# untitled.net
KiCad netlist of a schematic drawn in EAGLE
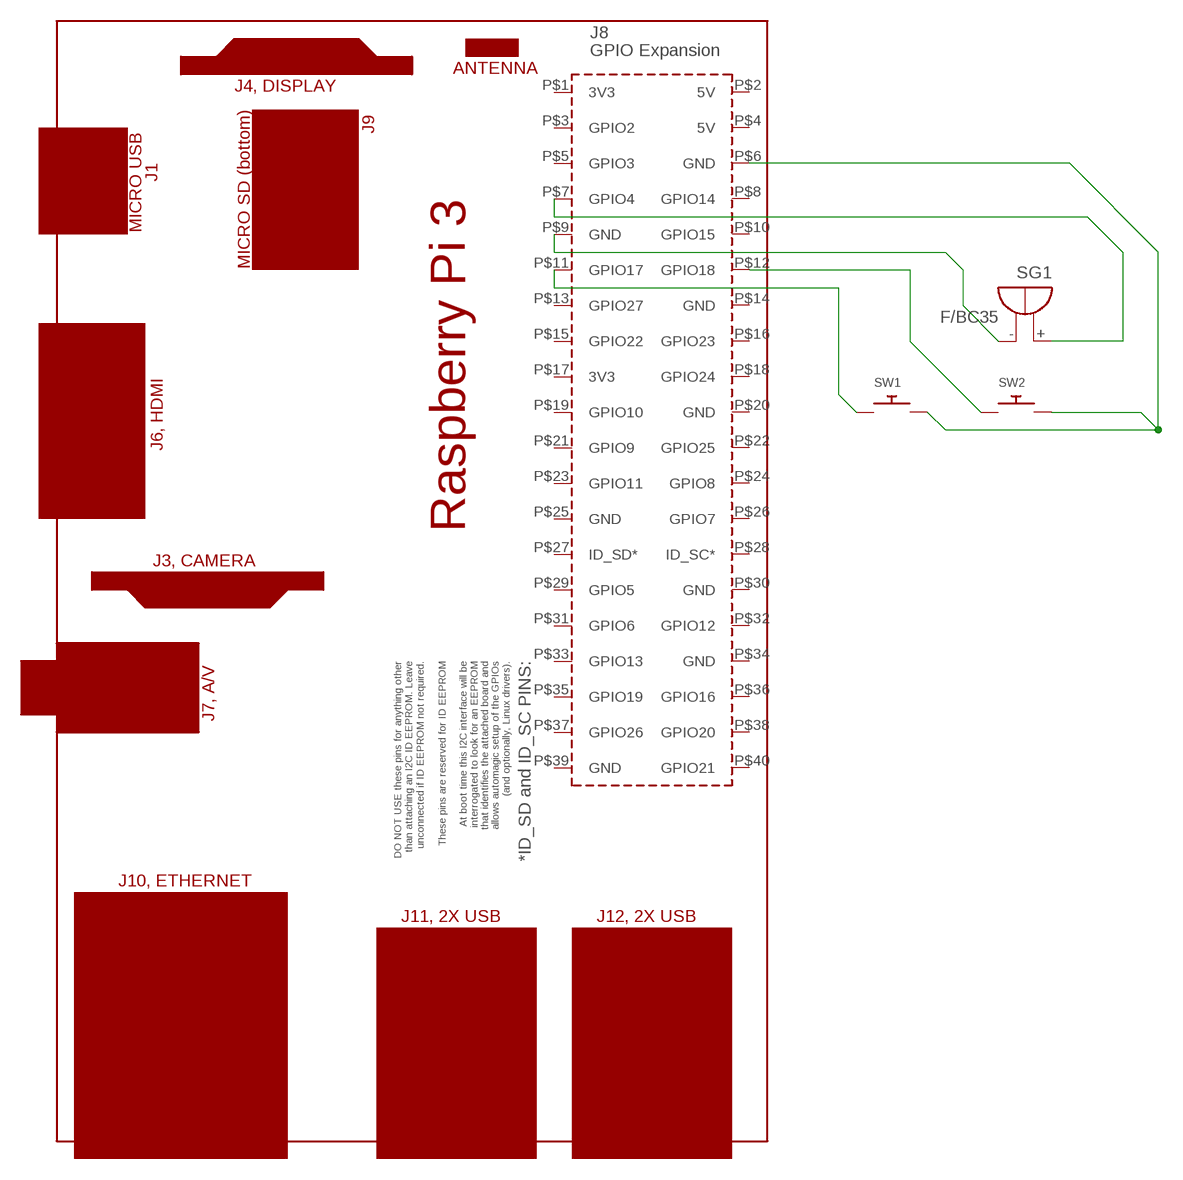
[diagram p0: schematic, sheet 1]

(export (version "E")
  (design (tool "Eeschema 10.0.6"))
  (components
    (comp (ref "PCB1")
      (value "RPI3RPI3")
      (footprint "eagle-import:RPI3")
      (libsource (lib "eagle-import") (part "RPI3RPI3"))
    )
    (comp (ref "SG1")
      (value "F/BC35")
      (footprint "eagle-import:F_BC35")
      (libsource (lib "eagle-import") (part "F/BC35"))
    )
    (comp (ref "SW1")
      (value "SWITCH_PUSHBUTTONSOFTTOUCHSMD_SJ")
      (footprint "eagle-import:PUSHBUTTON_SMD_SJ")
      (libsource (lib "eagle-import") (part "SWITCH_PUSHBUTTONSOFTTOUCHSMD_SJ"))
    )
    (comp (ref "SW2")
      (value "SWITCH_PUSHBUTTONSOFTTOUCHSMD_SJ")
      (footprint "eagle-import:PUSHBUTTON_SMD_SJ")
      (libsource (lib "eagle-import") (part "SWITCH_PUSHBUTTONSOFTTOUCHSMD_SJ"))
    )
  )
  (nets
    (net (code "1") (name "Net-(PCB1-GND-PadP$6)") (class "Default")
      (node (ref "PCB1") (pin "P$6") (pinfunction "GND_P$6") (pintype "bidirectional"))
      (node (ref "SW1") (pin "P$2") (pinfunction "P$2_P$2") (pintype "passive"))
      (node (ref "SW2") (pin "P$2") (pinfunction "P$2_P$2") (pintype "passive"))
    )
    (net (code "2") (name "Net-(PCB1-GND-PadP$9)") (class "Default")
      (node (ref "PCB1") (pin "P$9") (pinfunction "GND_P$9") (pintype "bidirectional"))
      (node (ref "SG1") (pin "-") (pinfunction "-_-") (pintype "passive"))
    )
    (net (code "3") (name "Net-(PCB1-GPIO4)") (class "Default")
      (node (ref "PCB1") (pin "P$7") (pinfunction "GPIO4_P$7") (pintype "bidirectional"))
      (node (ref "SG1") (pin "+") (pinfunction "+_+") (pintype "passive"))
    )
    (net (code "4") (name "Net-(PCB1-GPIO17)") (class "Default")
      (node (ref "PCB1") (pin "P$11") (pinfunction "GPIO17_P$11") (pintype "bidirectional"))
      (node (ref "SW1") (pin "P$1") (pinfunction "P$1_P$1") (pintype "passive"))
    )
    (net (code "5") (name "Net-(PCB1-GPIO18)") (class "Default")
      (node (ref "PCB1") (pin "P$12") (pinfunction "GPIO18_P$12") (pintype "bidirectional"))
      (node (ref "SW2") (pin "P$1") (pinfunction "P$1_P$1") (pintype "passive"))
    )
    (net (code "6") (name "unconnected-(PCB1-3V3-PadP$1)") (class "Default")
      (node (ref "PCB1") (pin "P$1") (pinfunction "3V3_P$1") (pintype "bidirectional"))
    )
    (net (code "7") (name "unconnected-(PCB1-3V3-PadP$17)") (class "Default")
      (node (ref "PCB1") (pin "P$17") (pinfunction "3V3_P$17") (pintype "bidirectional"))
    )
    (net (code "8") (name "unconnected-(PCB1-5V-PadP$2)") (class "Default")
      (node (ref "PCB1") (pin "P$2") (pinfunction "5V_P$2") (pintype "bidirectional"))
    )
    (net (code "9") (name "unconnected-(PCB1-5V-PadP$4)") (class "Default")
      (node (ref "PCB1") (pin "P$4") (pinfunction "5V_P$4") (pintype "bidirectional"))
    )
    (net (code "10") (name "unconnected-(PCB1-GND-PadP$14)") (class "Default")
      (node (ref "PCB1") (pin "P$14") (pinfunction "GND_P$14") (pintype "bidirectional"))
    )
    (net (code "11") (name "unconnected-(PCB1-GND-PadP$20)") (class "Default")
      (node (ref "PCB1") (pin "P$20") (pinfunction "GND_P$20") (pintype "bidirectional"))
    )
    (net (code "12") (name "unconnected-(PCB1-GND-PadP$25)") (class "Default")
      (node (ref "PCB1") (pin "P$25") (pinfunction "GND_P$25") (pintype "bidirectional"))
    )
    (net (code "13") (name "unconnected-(PCB1-GND-PadP$30)") (class "Default")
      (node (ref "PCB1") (pin "P$30") (pinfunction "GND_P$30") (pintype "bidirectional"))
    )
    (net (code "14") (name "unconnected-(PCB1-GND-PadP$34)") (class "Default")
      (node (ref "PCB1") (pin "P$34") (pinfunction "GND_P$34") (pintype "bidirectional"))
    )
    (net (code "15") (name "unconnected-(PCB1-GND-PadP$39)") (class "Default")
      (node (ref "PCB1") (pin "P$39") (pinfunction "GND_P$39") (pintype "bidirectional"))
    )
    (net (code "16") (name "unconnected-(PCB1-GPIO2-PadP$3)") (class "Default")
      (node (ref "PCB1") (pin "P$3") (pinfunction "GPIO2_P$3") (pintype "bidirectional"))
    )
    (net (code "17") (name "unconnected-(PCB1-GPIO3-PadP$5)") (class "Default")
      (node (ref "PCB1") (pin "P$5") (pinfunction "GPIO3_P$5") (pintype "bidirectional"))
    )
    (net (code "18") (name "unconnected-(PCB1-GPIO5-PadP$29)") (class "Default")
      (node (ref "PCB1") (pin "P$29") (pinfunction "GPIO5_P$29") (pintype "bidirectional"))
    )
    (net (code "19") (name "unconnected-(PCB1-GPIO6-PadP$31)") (class "Default")
      (node (ref "PCB1") (pin "P$31") (pinfunction "GPIO6_P$31") (pintype "bidirectional"))
    )
    (net (code "20") (name "unconnected-(PCB1-GPIO7-PadP$26)") (class "Default")
      (node (ref "PCB1") (pin "P$26") (pinfunction "GPIO7_P$26") (pintype "bidirectional"))
    )
    (net (code "21") (name "unconnected-(PCB1-GPIO8-PadP$24)") (class "Default")
      (node (ref "PCB1") (pin "P$24") (pinfunction "GPIO8_P$24") (pintype "bidirectional"))
    )
    (net (code "22") (name "unconnected-(PCB1-GPIO9-PadP$21)") (class "Default")
      (node (ref "PCB1") (pin "P$21") (pinfunction "GPIO9_P$21") (pintype "bidirectional"))
    )
    (net (code "23") (name "unconnected-(PCB1-GPIO10-PadP$19)") (class "Default")
      (node (ref "PCB1") (pin "P$19") (pinfunction "GPIO10_P$19") (pintype "bidirectional"))
    )
    (net (code "24") (name "unconnected-(PCB1-GPIO11-PadP$23)") (class "Default")
      (node (ref "PCB1") (pin "P$23") (pinfunction "GPIO11_P$23") (pintype "bidirectional"))
    )
    (net (code "25") (name "unconnected-(PCB1-GPIO12-PadP$32)") (class "Default")
      (node (ref "PCB1") (pin "P$32") (pinfunction "GPIO12_P$32") (pintype "bidirectional"))
    )
    (net (code "26") (name "unconnected-(PCB1-GPIO13-PadP$33)") (class "Default")
      (node (ref "PCB1") (pin "P$33") (pinfunction "GPIO13_P$33") (pintype "bidirectional"))
    )
    (net (code "27") (name "unconnected-(PCB1-GPIO14-PadP$8)") (class "Default")
      (node (ref "PCB1") (pin "P$8") (pinfunction "GPIO14_P$8") (pintype "bidirectional"))
    )
    (net (code "28") (name "unconnected-(PCB1-GPIO15-PadP$10)") (class "Default")
      (node (ref "PCB1") (pin "P$10") (pinfunction "GPIO15_P$10") (pintype "bidirectional"))
    )
    (net (code "29") (name "unconnected-(PCB1-GPIO16-PadP$36)") (class "Default")
      (node (ref "PCB1") (pin "P$36") (pinfunction "GPIO16_P$36") (pintype "bidirectional"))
    )
    (net (code "30") (name "unconnected-(PCB1-GPIO19-PadP$35)") (class "Default")
      (node (ref "PCB1") (pin "P$35") (pinfunction "GPIO19_P$35") (pintype "bidirectional"))
    )
    (net (code "31") (name "unconnected-(PCB1-GPIO20-PadP$38)") (class "Default")
      (node (ref "PCB1") (pin "P$38") (pinfunction "GPIO20_P$38") (pintype "bidirectional"))
    )
    (net (code "32") (name "unconnected-(PCB1-GPIO21-PadP$40)") (class "Default")
      (node (ref "PCB1") (pin "P$40") (pinfunction "GPIO21_P$40") (pintype "bidirectional"))
    )
    (net (code "33") (name "unconnected-(PCB1-GPIO22-PadP$15)") (class "Default")
      (node (ref "PCB1") (pin "P$15") (pinfunction "GPIO22_P$15") (pintype "bidirectional"))
    )
    (net (code "34") (name "unconnected-(PCB1-GPIO23-PadP$16)") (class "Default")
      (node (ref "PCB1") (pin "P$16") (pinfunction "GPIO23_P$16") (pintype "bidirectional"))
    )
    (net (code "35") (name "unconnected-(PCB1-GPIO24-PadP$18)") (class "Default")
      (node (ref "PCB1") (pin "P$18") (pinfunction "GPIO24_P$18") (pintype "bidirectional"))
    )
    (net (code "36") (name "unconnected-(PCB1-GPIO25-PadP$22)") (class "Default")
      (node (ref "PCB1") (pin "P$22") (pinfunction "GPIO25_P$22") (pintype "bidirectional"))
    )
    (net (code "37") (name "unconnected-(PCB1-GPIO26-PadP$37)") (class "Default")
      (node (ref "PCB1") (pin "P$37") (pinfunction "GPIO26_P$37") (pintype "bidirectional"))
    )
    (net (code "38") (name "unconnected-(PCB1-GPIO27-PadP$13)") (class "Default")
      (node (ref "PCB1") (pin "P$13") (pinfunction "GPIO27_P$13") (pintype "bidirectional"))
    )
    (net (code "39") (name "unconnected-(PCB1-ID_SC*-PadP$28)") (class "Default")
      (node (ref "PCB1") (pin "P$28") (pinfunction "ID_SC*_P$28") (pintype "bidirectional"))
    )
    (net (code "40") (name "unconnected-(PCB1-ID_SD*-PadP$27)") (class "Default")
      (node (ref "PCB1") (pin "P$27") (pinfunction "ID_SD*_P$27") (pintype "bidirectional"))
    )
  )
)
